# PMIC_Watchdog.net
KiCad netlist of a schematic drawn in Altium Designer
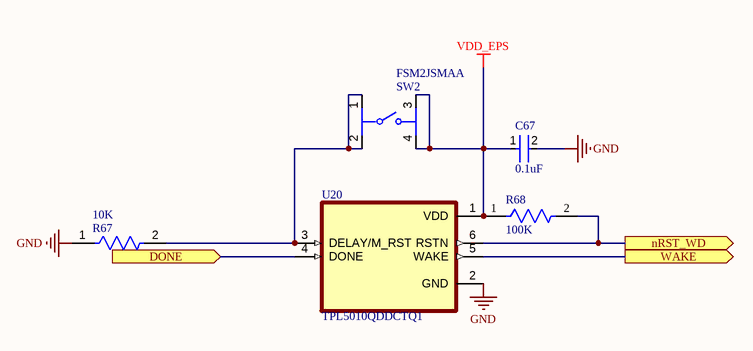
[diagram p0: PMIC_Watchdog.SchDoc]

(export (version "E")
  (design (tool "Eeschema 10.0.6"))
  (components
    (comp (ref "C67")
      (value "0.1uF")
      (footprint "FP-C0603C-CF-MFG")
      (description "CAP CER 0.1UF 50V X7R 0603")
      (fields (field (name "TOLERANCE") "0.1") (field (name "MANUFACTURER") "KEMET"))
      (libsource (lib "Altium Content Vault") (part "b4654b650e69147ec39a6b967a45e02"))
    )
    (comp (ref "R67")
      (value "10K")
      (footprint "FP-RK73B1J-MFG")
      (description "RES 10K OHM 5% 1/10W 0603")
      (fields (field (name "TOLERANCE") "5%"))
      (libsource (lib "Altium Content Vault") (part "1029c3af85768c4190bb7ad29bc67b5"))
    )
    (comp (ref "R68")
      (value "100K")
      (footprint "FP-ERA3A-MFG")
      (fields (field (name "TOLERANCE") "0.1%"))
      (libsource (lib "Altium Content Vault") (part "1029c3af85768c4190bb7ad29bc67b5"))
    )
    (comp (ref "SW2")
      (value "FSM2JSMAA")
      (footprint "FP-FSM2JSMAA-MFG")
      (description "SWITCH TACTILE SPST-NO 0.05A 24V")
      (fields
        (field (name "MANUFACTURER") "TE Connectivity")
        (field (name "OCTOPART") "https://octopart.com/fsm2jsmaa-te+connectivity-41720620")
      )
      (libsource (lib "Altium Content Vault") (part "b8895f3f4cefb76e1819d2863dba89b"))
    )
    (comp (ref "U20")
      (value "TPL5010QDDCTQ1")
      (footprint "SOT95P280X110-6N")
      (description "Automotive AEC-Q100, nano-powered system timer with watchdog function")
      (fields (field (name "MF") "Texas Instruments"))
      (libsource (lib "Hitesh Bhoyar") (part "TPL5010QDDCTQ1"))
    )
  )
  (nets
    (net (code "1") (name "/DONE") (class "Default")
      (node (ref "U20") (pin "4") (pinfunction "DONE_4") (pintype "input"))
    )
    (net (code "2") (name "/WAKE") (class "Default")
      (node (ref "U20") (pin "5") (pinfunction "WAKE_5") (pintype "output"))
    )
    (net (code "3") (name "/nRST_WD") (class "Default")
      (node (ref "R68") (pin "2") (pinfunction "2_2") (pintype "passive"))
      (node (ref "U20") (pin "6") (pinfunction "RSTN_6") (pintype "output"))
    )
    (net (code "4") (name "GND") (class "Default")
      (node (ref "C67") (pin "2") (pinfunction "2_2") (pintype "passive"))
      (node (ref "R67") (pin "1") (pinfunction "1_1") (pintype "passive"))
      (node (ref "U20") (pin "2") (pinfunction "GND_2") (pintype "power_in"))
    )
    (net (code "5") (name "Net-(U20-DELAY{slash}M_RST)") (class "Default")
      (node (ref "R67") (pin "2") (pinfunction "2_2") (pintype "passive"))
      (node (ref "SW2") (pin "1") (pinfunction "1_1") (pintype "passive"))
      (node (ref "SW2") (pin "2") (pinfunction "2_2") (pintype "passive"))
      (node (ref "U20") (pin "3") (pinfunction "DELAY/M_RST_3") (pintype "input"))
    )
    (net (code "6") (name "VDD_EPS") (class "Default")
      (node (ref "C67") (pin "1") (pinfunction "1_1") (pintype "passive"))
      (node (ref "R68") (pin "1") (pinfunction "1_1") (pintype "passive"))
      (node (ref "SW2") (pin "3") (pinfunction "3_3") (pintype "passive"))
      (node (ref "SW2") (pin "4") (pinfunction "4_4") (pintype "passive"))
      (node (ref "U20") (pin "1") (pinfunction "VDD_1") (pintype "power_in"))
    )
  )
)
